# pgab.net
KiCad netlist of a schematic drawn in EAGLE
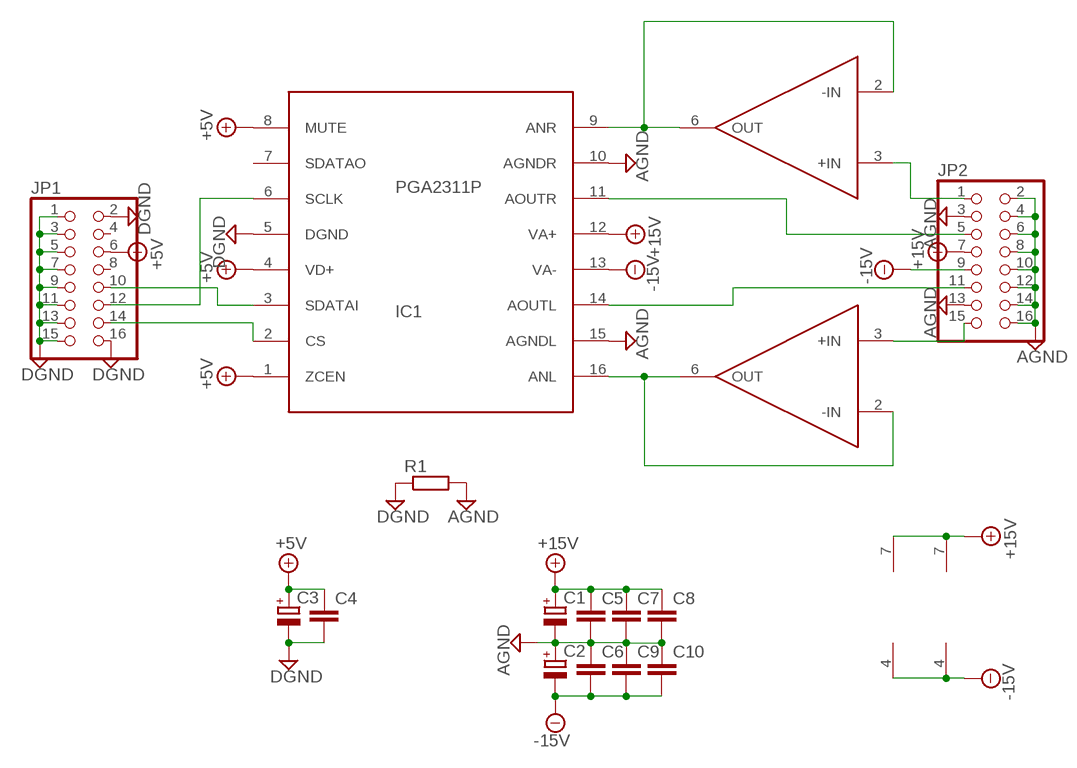
[diagram p0: schematic, sheet 1]

(export (version "E")
  (design (tool "Eeschema 10.0.6"))
  (components
    (comp (ref "C1")
      (value "CPOL-EUE3.5-8")
      (footprint "eagle-import:E3,5-8")
      (libsource (lib "eagle-import") (part "CPOL-EUE3.5-8"))
    )
    (comp (ref "C2")
      (value "CPOL-EUE3.5-8")
      (footprint "eagle-import:E3,5-8")
      (libsource (lib "eagle-import") (part "CPOL-EUE3.5-8"))
    )
    (comp (ref "C3")
      (value "CPOL-EUE3.5-8")
      (footprint "eagle-import:E3,5-8")
      (libsource (lib "eagle-import") (part "CPOL-EUE3.5-8"))
    )
    (comp (ref "C4")
      (value "C-EU025-025X050")
      (footprint "eagle-import:C025-025X050")
      (libsource (lib "eagle-import") (part "C-EU025-025X050"))
    )
    (comp (ref "C5")
      (value "C-EU025-025X050")
      (footprint "eagle-import:C025-025X050")
      (libsource (lib "eagle-import") (part "C-EU025-025X050"))
    )
    (comp (ref "C6")
      (value "C-EU025-025X050")
      (footprint "eagle-import:C025-025X050")
      (libsource (lib "eagle-import") (part "C-EU025-025X050"))
    )
    (comp (ref "C7")
      (value "C-EU025-025X050")
      (footprint "eagle-import:C025-025X050")
      (libsource (lib "eagle-import") (part "C-EU025-025X050"))
    )
    (comp (ref "C8")
      (value "C-EU025-025X050")
      (footprint "eagle-import:C025-025X050")
      (libsource (lib "eagle-import") (part "C-EU025-025X050"))
    )
    (comp (ref "C9")
      (value "C-EU025-025X050")
      (footprint "eagle-import:C025-025X050")
      (libsource (lib "eagle-import") (part "C-EU025-025X050"))
    )
    (comp (ref "C10")
      (value "C-EU025-025X050")
      (footprint "eagle-import:C025-025X050")
      (libsource (lib "eagle-import") (part "C-EU025-025X050"))
    )
    (comp (ref "IC1")
      (value "PGA2311P")
      (footprint "eagle-import:DIL16")
      (libsource (lib "eagle-import") (part "PGA2311P"))
    )
    (comp (ref "JP1")
      (value "PINHD-2X8")
      (footprint "eagle-import:2X08")
      (libsource (lib "eagle-import") (part "PINHD-2X8"))
    )
    (comp (ref "JP2")
      (value "PINHD-2X8")
      (footprint "eagle-import:2X08")
      (libsource (lib "eagle-import") (part "PINHD-2X8"))
    )
    (comp (ref "R1")
      (value "R-EU_0207/10")
      (footprint "eagle-import:0207_10")
      (libsource (lib "eagle-import") (part "R-EU_0207/10"))
    )
    (comp (ref "U1")
      (value "OPA627BP")
      (footprint "eagle-import:DIL08")
      (libsource (lib "eagle-import") (part "OPA627BP"))
    )
    (comp (ref "U2")
      (value "OPA627BP")
      (footprint "eagle-import:DIL08")
      (libsource (lib "eagle-import") (part "OPA627BP"))
    )
  )
  (nets
    (net (code "1") (name "+5V") (class "Default")
      (node (ref "C3") (pin "+") (pinfunction "+_+") (pintype "passive"))
      (node (ref "C4") (pin "1") (pinfunction "1_1") (pintype "passive"))
      (node (ref "IC1") (pin "1") (pinfunction "ZCEN_1") (pintype "input"))
      (node (ref "IC1") (pin "4") (pinfunction "VD+_4") (pintype "power_in"))
      (node (ref "IC1") (pin "8") (pinfunction "MUTE_8") (pintype "input"))
      (node (ref "JP1") (pin "6") (pinfunction "6_6") (pintype "passive"))
    )
    (net (code "2") (name "+15V") (class "Default")
      (node (ref "C1") (pin "+") (pinfunction "+_+") (pintype "passive"))
      (node (ref "C5") (pin "1") (pinfunction "1_1") (pintype "passive"))
      (node (ref "C7") (pin "1") (pinfunction "1_1") (pintype "passive"))
      (node (ref "C8") (pin "1") (pinfunction "1_1") (pintype "passive"))
      (node (ref "IC1") (pin "12") (pinfunction "VA+_12") (pintype "power_in"))
      (node (ref "JP2") (pin "7") (pinfunction "7_7") (pintype "passive"))
      (node (ref "U1") (pin "7") (pinfunction "V+_7") (pintype "bidirectional"))
      (node (ref "U2") (pin "7") (pinfunction "V+_7") (pintype "bidirectional"))
    )
    (net (code "3") (name "-15V") (class "Default")
      (node (ref "C10") (pin "2") (pinfunction "2_2") (pintype "passive"))
      (node (ref "C2") (pin "-") (pinfunction "-_-") (pintype "passive"))
      (node (ref "C6") (pin "2") (pinfunction "2_2") (pintype "passive"))
      (node (ref "C9") (pin "2") (pinfunction "2_2") (pintype "passive"))
      (node (ref "IC1") (pin "13") (pinfunction "VA-_13") (pintype "power_in"))
      (node (ref "JP2") (pin "9") (pinfunction "9_9") (pintype "passive"))
      (node (ref "U1") (pin "4") (pinfunction "V-_4") (pintype "bidirectional"))
      (node (ref "U2") (pin "4") (pinfunction "V-_4") (pintype "bidirectional"))
    )
    (net (code "4") (name "AGND") (class "Default")
      (node (ref "C1") (pin "-") (pinfunction "-_-") (pintype "passive"))
      (node (ref "C10") (pin "1") (pinfunction "1_1") (pintype "passive"))
      (node (ref "C2") (pin "+") (pinfunction "+_+") (pintype "passive"))
      (node (ref "C5") (pin "2") (pinfunction "2_2") (pintype "passive"))
      (node (ref "C6") (pin "1") (pinfunction "1_1") (pintype "passive"))
      (node (ref "C7") (pin "2") (pinfunction "2_2") (pintype "passive"))
      (node (ref "C8") (pin "2") (pinfunction "2_2") (pintype "passive"))
      (node (ref "C9") (pin "1") (pinfunction "1_1") (pintype "passive"))
      (node (ref "IC1") (pin "10") (pinfunction "AGNDR_10") (pintype "power_in"))
      (node (ref "IC1") (pin "15") (pinfunction "AGNDL_15") (pintype "power_in"))
      (node (ref "JP2") (pin "10") (pinfunction "10_10") (pintype "passive"))
      (node (ref "JP2") (pin "12") (pinfunction "12_12") (pintype "passive"))
      (node (ref "JP2") (pin "13") (pinfunction "13_13") (pintype "passive"))
      (node (ref "JP2") (pin "14") (pinfunction "14_14") (pintype "passive"))
      (node (ref "JP2") (pin "16") (pinfunction "16_16") (pintype "passive"))
      (node (ref "JP2") (pin "2") (pinfunction "2_2") (pintype "passive"))
      (node (ref "JP2") (pin "3") (pinfunction "3_3") (pintype "passive"))
      (node (ref "JP2") (pin "4") (pinfunction "4_4") (pintype "passive"))
      (node (ref "JP2") (pin "6") (pinfunction "6_6") (pintype "passive"))
      (node (ref "JP2") (pin "8") (pinfunction "8_8") (pintype "passive"))
      (node (ref "R1") (pin "2") (pinfunction "2_2") (pintype "passive"))
    )
    (net (code "5") (name "DGND") (class "Default")
      (node (ref "C3") (pin "-") (pinfunction "-_-") (pintype "passive"))
      (node (ref "C4") (pin "2") (pinfunction "2_2") (pintype "passive"))
      (node (ref "IC1") (pin "5") (pinfunction "DGND_5") (pintype "power_in"))
      (node (ref "JP1") (pin "1") (pinfunction "1_1") (pintype "passive"))
      (node (ref "JP1") (pin "11") (pinfunction "11_11") (pintype "passive"))
      (node (ref "JP1") (pin "13") (pinfunction "13_13") (pintype "passive"))
      (node (ref "JP1") (pin "15") (pinfunction "15_15") (pintype "passive"))
      (node (ref "JP1") (pin "16") (pinfunction "16_16") (pintype "passive"))
      (node (ref "JP1") (pin "2") (pinfunction "2_2") (pintype "passive"))
      (node (ref "JP1") (pin "3") (pinfunction "3_3") (pintype "passive"))
      (node (ref "JP1") (pin "5") (pinfunction "5_5") (pintype "passive"))
      (node (ref "JP1") (pin "7") (pinfunction "7_7") (pintype "passive"))
      (node (ref "JP1") (pin "9") (pinfunction "9_9") (pintype "passive"))
      (node (ref "R1") (pin "1") (pinfunction "1_1") (pintype "passive"))
    )
    (net (code "6") (name "Net-(IC1-ANL)") (class "Default")
      (node (ref "IC1") (pin "16") (pinfunction "ANL_16") (pintype "input"))
      (node (ref "U2") (pin "2") (pinfunction "-IN_2") (pintype "bidirectional"))
      (node (ref "U2") (pin "6") (pinfunction "OUT_6") (pintype "bidirectional"))
    )
    (net (code "7") (name "Net-(IC1-ANR)") (class "Default")
      (node (ref "IC1") (pin "9") (pinfunction "ANR_9") (pintype "input"))
      (node (ref "U1") (pin "2") (pinfunction "-IN_2") (pintype "bidirectional"))
      (node (ref "U1") (pin "6") (pinfunction "OUT_6") (pintype "bidirectional"))
    )
    (net (code "8") (name "Net-(IC1-AOUTL)") (class "Default")
      (node (ref "IC1") (pin "14") (pinfunction "AOUTL_14") (pintype "output"))
      (node (ref "JP2") (pin "11") (pinfunction "11_11") (pintype "passive"))
    )
    (net (code "9") (name "Net-(IC1-AOUTR)") (class "Default")
      (node (ref "IC1") (pin "11") (pinfunction "AOUTR_11") (pintype "output"))
      (node (ref "JP2") (pin "5") (pinfunction "5_5") (pintype "passive"))
    )
    (net (code "10") (name "Net-(IC1-CS)") (class "Default")
      (node (ref "IC1") (pin "2") (pinfunction "CS_2") (pintype "bidirectional"))
      (node (ref "JP1") (pin "14") (pinfunction "14_14") (pintype "passive"))
    )
    (net (code "11") (name "Net-(IC1-SCLK)") (class "Default")
      (node (ref "IC1") (pin "6") (pinfunction "SCLK_6") (pintype "input"))
      (node (ref "JP1") (pin "12") (pinfunction "12_12") (pintype "passive"))
    )
    (net (code "12") (name "Net-(IC1-SDATAI)") (class "Default")
      (node (ref "IC1") (pin "3") (pinfunction "SDATAI_3") (pintype "input"))
      (node (ref "JP1") (pin "10") (pinfunction "10_10") (pintype "passive"))
    )
    (net (code "13") (name "Net-(U1A-+IN)") (class "Default")
      (node (ref "JP2") (pin "1") (pinfunction "1_1") (pintype "passive"))
      (node (ref "U1") (pin "3") (pinfunction "+IN_3") (pintype "bidirectional"))
    )
    (net (code "14") (name "Net-(U2A-+IN)") (class "Default")
      (node (ref "JP2") (pin "15") (pinfunction "15_15") (pintype "passive"))
      (node (ref "U2") (pin "3") (pinfunction "+IN_3") (pintype "bidirectional"))
    )
    (net (code "15") (name "unconnected-(IC1-SDATAO-Pad7)") (class "Default")
      (node (ref "IC1") (pin "7") (pinfunction "SDATAO_7") (pintype "output"))
    )
    (net (code "16") (name "unconnected-(JP1-Pad4)") (class "Default")
      (node (ref "JP1") (pin "4") (pinfunction "4_4") (pintype "passive"))
    )
    (net (code "17") (name "unconnected-(JP1-Pad8)") (class "Default")
      (node (ref "JP1") (pin "8") (pinfunction "8_8") (pintype "passive"))
    )
  )
)
